# 2_OTHER.net
KiCad netlist of a schematic drawn in Altium Designer
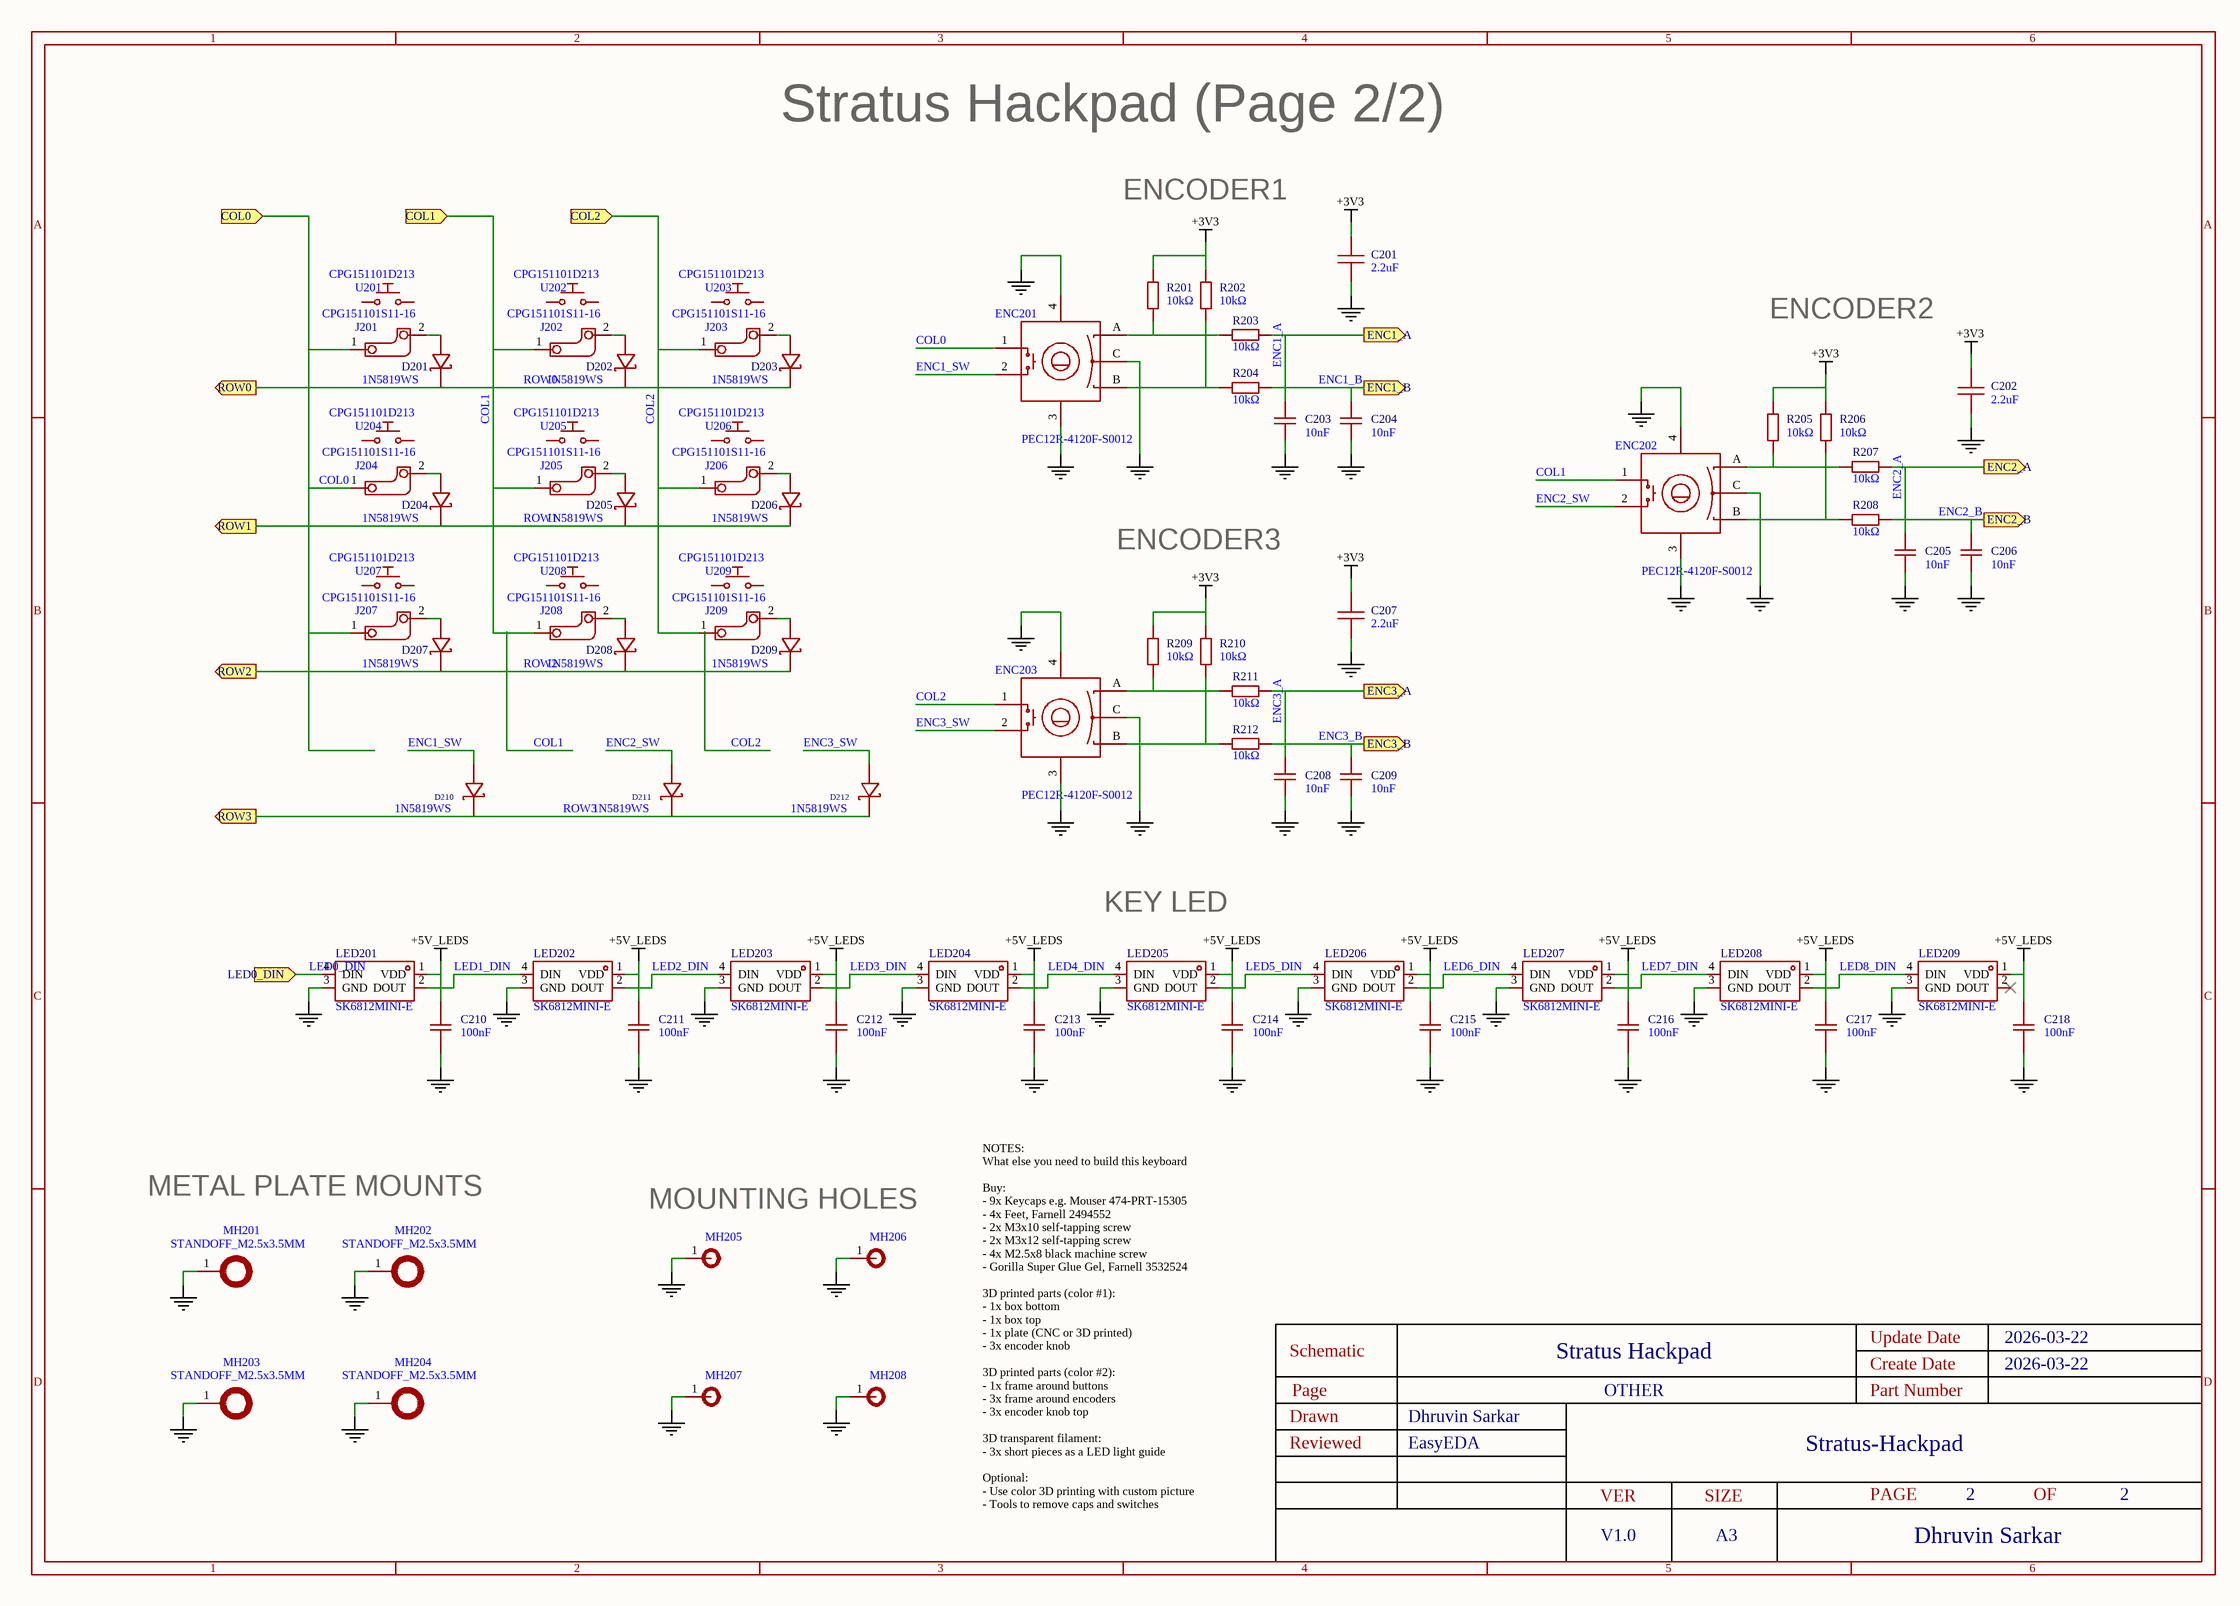
[diagram p0: 2_OTHER.schdoc]

(export (version "E")
  (design (tool "Eeschema 10.0.6"))
  (components
    (comp (ref "C201")
      (value "2.2uF")
      (footprint "C0402")
      (fields
        (field (name "MANUFACTURER") "SAMSUNG(三星)")
        (field (name "MANUFACTURER PART") "CL05A225MQ5NSNC")
        (field (name "TOLERANCE") "±20%")
      )
      (libsource (lib "altium-import") (part "root_1_CL05A225MQ5NSNC_"))
    )
    (comp (ref "C202")
      (value "2.2uF")
      (footprint "C0402")
      (fields
        (field (name "MANUFACTURER") "SAMSUNG(三星)")
        (field (name "MANUFACTURER PART") "CL05A225MQ5NSNC")
        (field (name "TOLERANCE") "±20%")
      )
      (libsource (lib "altium-import") (part "root_1_CL05A225MQ5NSNC_"))
    )
    (comp (ref "C203")
      (value "10nF")
      (footprint "C0402")
      (fields
        (field (name "MANUFACTURER") "SAMSUNG(三星)")
        (field (name "MANUFACTURER PART") "CL05B103KB5NNNC")
        (field (name "TOLERANCE") "±10%")
      )
      (libsource (lib "altium-import") (part "root_1_CL05B103KB5NNNC_"))
    )
    (comp (ref "C204")
      (value "10nF")
      (footprint "C0402")
      (fields
        (field (name "MANUFACTURER") "SAMSUNG(三星)")
        (field (name "MANUFACTURER PART") "CL05B103KB5NNNC")
        (field (name "TOLERANCE") "±10%")
      )
      (libsource (lib "altium-import") (part "root_1_CL05B103KB5NNNC_"))
    )
    (comp (ref "C205")
      (value "10nF")
      (footprint "C0402")
      (fields
        (field (name "MANUFACTURER") "SAMSUNG(三星)")
        (field (name "MANUFACTURER PART") "CL05B103KB5NNNC")
        (field (name "TOLERANCE") "±10%")
      )
      (libsource (lib "altium-import") (part "root_1_CL05B103KB5NNNC_"))
    )
    (comp (ref "C206")
      (value "10nF")
      (footprint "C0402")
      (fields
        (field (name "MANUFACTURER") "SAMSUNG(三星)")
        (field (name "MANUFACTURER PART") "CL05B103KB5NNNC")
        (field (name "TOLERANCE") "±10%")
      )
      (libsource (lib "altium-import") (part "root_1_CL05B103KB5NNNC_"))
    )
    (comp (ref "C207")
      (value "2.2uF")
      (footprint "C0402")
      (fields
        (field (name "MANUFACTURER") "SAMSUNG(三星)")
        (field (name "MANUFACTURER PART") "CL05A225MQ5NSNC")
        (field (name "TOLERANCE") "±20%")
      )
      (libsource (lib "altium-import") (part "root_1_CL05A225MQ5NSNC_"))
    )
    (comp (ref "C208")
      (value "10nF")
      (footprint "C0402")
      (fields
        (field (name "MANUFACTURER") "SAMSUNG(三星)")
        (field (name "MANUFACTURER PART") "CL05B103KB5NNNC")
        (field (name "TOLERANCE") "±10%")
      )
      (libsource (lib "altium-import") (part "root_1_CL05B103KB5NNNC_"))
    )
    (comp (ref "C209")
      (value "10nF")
      (footprint "C0402")
      (fields
        (field (name "MANUFACTURER") "SAMSUNG(三星)")
        (field (name "MANUFACTURER PART") "CL05B103KB5NNNC")
        (field (name "TOLERANCE") "±10%")
      )
      (libsource (lib "altium-import") (part "root_1_CL05B103KB5NNNC_"))
    )
    (comp (ref "C210")
      (value "100nF")
      (footprint "C0402")
      (fields
        (field (name "MANUFACTURER") "SAMSUNG(三星)")
        (field (name "MANUFACTURER PART") "CL05B104KO5NNNC")
        (field (name "TOLERANCE") "±10%")
      )
      (libsource (lib "altium-import") (part "root_1_CL05B104KO5NNNC_"))
    )
    (comp (ref "C211")
      (value "100nF")
      (footprint "C0402")
      (fields
        (field (name "MANUFACTURER") "SAMSUNG(三星)")
        (field (name "MANUFACTURER PART") "CL05B104KO5NNNC")
        (field (name "TOLERANCE") "±10%")
      )
      (libsource (lib "altium-import") (part "root_1_CL05B104KO5NNNC_"))
    )
    (comp (ref "C212")
      (value "100nF")
      (footprint "C0402")
      (fields
        (field (name "MANUFACTURER") "SAMSUNG(三星)")
        (field (name "MANUFACTURER PART") "CL05B104KO5NNNC")
        (field (name "TOLERANCE") "±10%")
      )
      (libsource (lib "altium-import") (part "root_1_CL05B104KO5NNNC_"))
    )
    (comp (ref "C213")
      (value "100nF")
      (footprint "C0402")
      (fields
        (field (name "MANUFACTURER") "SAMSUNG(三星)")
        (field (name "MANUFACTURER PART") "CL05B104KO5NNNC")
        (field (name "TOLERANCE") "±10%")
      )
      (libsource (lib "altium-import") (part "root_1_CL05B104KO5NNNC_"))
    )
    (comp (ref "C214")
      (value "100nF")
      (footprint "C0402")
      (fields
        (field (name "MANUFACTURER") "SAMSUNG(三星)")
        (field (name "MANUFACTURER PART") "CL05B104KO5NNNC")
        (field (name "TOLERANCE") "±10%")
      )
      (libsource (lib "altium-import") (part "root_1_CL05B104KO5NNNC_"))
    )
    (comp (ref "C215")
      (value "100nF")
      (footprint "C0402")
      (fields
        (field (name "MANUFACTURER") "SAMSUNG(三星)")
        (field (name "MANUFACTURER PART") "CL05B104KO5NNNC")
        (field (name "TOLERANCE") "±10%")
      )
      (libsource (lib "altium-import") (part "root_1_CL05B104KO5NNNC_"))
    )
    (comp (ref "C216")
      (value "100nF")
      (footprint "C0402")
      (fields
        (field (name "MANUFACTURER") "SAMSUNG(三星)")
        (field (name "MANUFACTURER PART") "CL05B104KO5NNNC")
        (field (name "TOLERANCE") "±10%")
      )
      (libsource (lib "altium-import") (part "root_1_CL05B104KO5NNNC_"))
    )
    (comp (ref "C217")
      (value "100nF")
      (footprint "C0402")
      (fields
        (field (name "MANUFACTURER") "SAMSUNG(三星)")
        (field (name "MANUFACTURER PART") "CL05B104KO5NNNC")
        (field (name "TOLERANCE") "±10%")
      )
      (libsource (lib "altium-import") (part "root_1_CL05B104KO5NNNC_"))
    )
    (comp (ref "C218")
      (value "100nF")
      (footprint "C0402")
      (fields
        (field (name "MANUFACTURER") "SAMSUNG(三星)")
        (field (name "MANUFACTURER PART") "CL05B104KO5NNNC")
        (field (name "TOLERANCE") "±10%")
      )
      (libsource (lib "altium-import") (part "root_1_CL05B104KO5NNNC_"))
    )
    (comp (ref "D201")
      (value "1N5819WS")
      (footprint "SOD-323_L1.8-W1.3-LS2.5-RD")
      (fields (field (name "MANUFACTURER") "Hottech(合科泰)"))
      (libsource (lib "altium-import") (part "root_1_1N5819WS_C191023_"))
    )
    (comp (ref "D202")
      (value "1N5819WS")
      (footprint "SOD-323_L1.8-W1.3-LS2.5-RD")
      (fields (field (name "MANUFACTURER") "Hottech(合科泰)"))
      (libsource (lib "altium-import") (part "root_1_1N5819WS_C191023_"))
    )
    (comp (ref "D203")
      (value "1N5819WS")
      (footprint "SOD-323_L1.8-W1.3-LS2.5-RD")
      (fields (field (name "MANUFACTURER") "Hottech(合科泰)"))
      (libsource (lib "altium-import") (part "root_1_1N5819WS_C191023_"))
    )
    (comp (ref "D204")
      (value "1N5819WS")
      (footprint "SOD-323_L1.8-W1.3-LS2.5-RD")
      (fields (field (name "MANUFACTURER") "Hottech(合科泰)"))
      (libsource (lib "altium-import") (part "root_1_1N5819WS_C191023_"))
    )
    (comp (ref "D205")
      (value "1N5819WS")
      (footprint "SOD-323_L1.8-W1.3-LS2.5-RD")
      (fields (field (name "MANUFACTURER") "Hottech(合科泰)"))
      (libsource (lib "altium-import") (part "root_1_1N5819WS_C191023_"))
    )
    (comp (ref "D206")
      (value "1N5819WS")
      (footprint "SOD-323_L1.8-W1.3-LS2.5-RD")
      (fields (field (name "MANUFACTURER") "Hottech(合科泰)"))
      (libsource (lib "altium-import") (part "root_1_1N5819WS_C191023_"))
    )
    (comp (ref "D207")
      (value "1N5819WS")
      (footprint "SOD-323_L1.8-W1.3-LS2.5-RD")
      (fields (field (name "MANUFACTURER") "Hottech(合科泰)"))
      (libsource (lib "altium-import") (part "root_1_1N5819WS_C191023_"))
    )
    (comp (ref "D208")
      (value "1N5819WS")
      (footprint "SOD-323_L1.8-W1.3-LS2.5-RD")
      (fields (field (name "MANUFACTURER") "Hottech(合科泰)"))
      (libsource (lib "altium-import") (part "root_1_1N5819WS_C191023_"))
    )
    (comp (ref "D209")
      (value "1N5819WS")
      (footprint "SOD-323_L1.8-W1.3-LS2.5-RD")
      (fields (field (name "MANUFACTURER") "Hottech(合科泰)"))
      (libsource (lib "altium-import") (part "root_1_1N5819WS_C191023_"))
    )
    (comp (ref "D210")
      (value "1N5819WS")
      (footprint "SOD-323_L1.8-W1.3-LS2.5-RD")
      (fields (field (name "MANUFACTURER") "Hottech(合科泰)"))
      (libsource (lib "altium-import") (part "root_1_1N5819WS_C191023_"))
    )
    (comp (ref "D211")
      (value "1N5819WS")
      (footprint "SOD-323_L1.8-W1.3-LS2.5-RD")
      (fields (field (name "MANUFACTURER") "Hottech(合科泰)"))
      (libsource (lib "altium-import") (part "root_1_1N5819WS_C191023_"))
    )
    (comp (ref "D212")
      (value "1N5819WS")
      (footprint "SOD-323_L1.8-W1.3-LS2.5-RD")
      (fields (field (name "MANUFACTURER") "Hottech(合科泰)"))
      (libsource (lib "altium-import") (part "root_1_1N5819WS_C191023_"))
    )
    (comp (ref "ENC201")
      (value "PEC12R-4120F-S0012")
      (footprint "SW-TH_PEC12R-4120F-S0012_1")
      (fields (field (name "MANUFACTURER") "BOURNS"))
      (libsource (lib "altium-import") (part "root_3_mirrored_PEC12R-4120F-S0012_RF_v1.0_"))
    )
    (comp (ref "ENC202")
      (value "PEC12R-4120F-S0012")
      (footprint "SW-TH_PEC12R-4120F-S0012_1")
      (fields (field (name "MANUFACTURER") "BOURNS"))
      (libsource (lib "altium-import") (part "root_3_mirrored_PEC12R-4120F-S0012_RF_v1.0_"))
    )
    (comp (ref "ENC203")
      (value "PEC12R-4120F-S0012")
      (footprint "SW-TH_PEC12R-4120F-S0012_1")
      (fields (field (name "MANUFACTURER") "BOURNS"))
      (libsource (lib "altium-import") (part "root_3_mirrored_PEC12R-4120F-S0012_RF_v1.0_"))
    )
    (comp (ref "J201")
      (value "CPG151101S11-16")
      (footprint "SMD_KEYBOARD-SW")
      (fields (field (name "MANUFACTURER") "Kailh(凯华)"))
      (libsource (lib "altium-import") (part "root_0_CPG151101S11-16_DS_v1.0_"))
    )
    (comp (ref "J202")
      (value "CPG151101S11-16")
      (footprint "SMD_KEYBOARD-SW")
      (fields (field (name "MANUFACTURER") "Kailh(凯华)"))
      (libsource (lib "altium-import") (part "root_0_CPG151101S11-16_DS_v1.0_"))
    )
    (comp (ref "J203")
      (value "CPG151101S11-16")
      (footprint "SMD_KEYBOARD-SW")
      (fields (field (name "MANUFACTURER") "Kailh(凯华)"))
      (libsource (lib "altium-import") (part "root_0_CPG151101S11-16_DS_v1.0_"))
    )
    (comp (ref "J204")
      (value "CPG151101S11-16")
      (footprint "SMD_KEYBOARD-SW")
      (fields (field (name "MANUFACTURER") "Kailh(凯华)"))
      (libsource (lib "altium-import") (part "root_0_CPG151101S11-16_DS_v1.0_"))
    )
    (comp (ref "J205")
      (value "CPG151101S11-16")
      (footprint "SMD_KEYBOARD-SW")
      (fields (field (name "MANUFACTURER") "Kailh(凯华)"))
      (libsource (lib "altium-import") (part "root_0_CPG151101S11-16_DS_v1.0_"))
    )
    (comp (ref "J206")
      (value "CPG151101S11-16")
      (footprint "SMD_KEYBOARD-SW")
      (fields (field (name "MANUFACTURER") "Kailh(凯华)"))
      (libsource (lib "altium-import") (part "root_0_CPG151101S11-16_DS_v1.0_"))
    )
    (comp (ref "J207")
      (value "CPG151101S11-16")
      (footprint "SMD_KEYBOARD-SW")
      (fields (field (name "MANUFACTURER") "Kailh(凯华)"))
      (libsource (lib "altium-import") (part "root_0_CPG151101S11-16_DS_v1.0_"))
    )
    (comp (ref "J208")
      (value "CPG151101S11-16")
      (footprint "SMD_KEYBOARD-SW")
      (fields (field (name "MANUFACTURER") "Kailh(凯华)"))
      (libsource (lib "altium-import") (part "root_0_CPG151101S11-16_DS_v1.0_"))
    )
    (comp (ref "J209")
      (value "CPG151101S11-16")
      (footprint "SMD_KEYBOARD-SW")
      (fields (field (name "MANUFACTURER") "Kailh(凯华)"))
      (libsource (lib "altium-import") (part "root_0_CPG151101S11-16_DS_v1.0_"))
    )
    (comp (ref "LED201")
      (value "SK6812MINI-E")
      (footprint "LED-SMD_L3.2-W2.8-TR")
      (fields (field (name "MANUFACTURER") "欧思科光电"))
      (libsource (lib "altium-import") (part "root_0_mirrored_SK6812MINI-E_C5149201_"))
    )
    (comp (ref "LED202")
      (value "SK6812MINI-E")
      (footprint "LED-SMD_L3.2-W2.8-TR")
      (fields (field (name "MANUFACTURER") "欧思科光电"))
      (libsource (lib "altium-import") (part "root_0_mirrored_SK6812MINI-E_C5149201_"))
    )
    (comp (ref "LED203")
      (value "SK6812MINI-E")
      (footprint "LED-SMD_L3.2-W2.8-TR")
      (fields (field (name "MANUFACTURER") "欧思科光电"))
      (libsource (lib "altium-import") (part "root_0_mirrored_SK6812MINI-E_C5149201_"))
    )
    (comp (ref "LED204")
      (value "SK6812MINI-E")
      (footprint "LED-SMD_L3.2-W2.8-TR")
      (fields (field (name "MANUFACTURER") "欧思科光电"))
      (libsource (lib "altium-import") (part "root_0_mirrored_SK6812MINI-E_C5149201_"))
    )
    (comp (ref "LED205")
      (value "SK6812MINI-E")
      (footprint "LED-SMD_L3.2-W2.8-TR")
      (fields (field (name "MANUFACTURER") "欧思科光电"))
      (libsource (lib "altium-import") (part "root_0_mirrored_SK6812MINI-E_C5149201_"))
    )
    (comp (ref "LED206")
      (value "SK6812MINI-E")
      (footprint "LED-SMD_L3.2-W2.8-TR")
      (fields (field (name "MANUFACTURER") "欧思科光电"))
      (libsource (lib "altium-import") (part "root_0_mirrored_SK6812MINI-E_C5149201_"))
    )
    (comp (ref "LED207")
      (value "SK6812MINI-E")
      (footprint "LED-SMD_L3.2-W2.8-TR")
      (fields (field (name "MANUFACTURER") "欧思科光电"))
      (libsource (lib "altium-import") (part "root_0_mirrored_SK6812MINI-E_C5149201_"))
    )
    (comp (ref "LED208")
      (value "SK6812MINI-E")
      (footprint "LED-SMD_L3.2-W2.8-TR")
      (fields (field (name "MANUFACTURER") "欧思科光电"))
      (libsource (lib "altium-import") (part "root_0_mirrored_SK6812MINI-E_C5149201_"))
    )
    (comp (ref "LED209")
      (value "SK6812MINI-E")
      (footprint "LED-SMD_L3.2-W2.8-TR")
      (fields (field (name "MANUFACTURER") "欧思科光电"))
      (libsource (lib "altium-import") (part "root_0_mirrored_SK6812MINI-E_C5149201_"))
    )
    (comp (ref "MH201")
      (value "STANDOFF_M2.5x3.5MM")
      (footprint "STANDOFF_M2.5x3.5MM_RF_v1.0")
      (fields (field (name "MANUFACTURER") "WURTH ELEKTRONIK") (field (name "PART NUMBER") "9774035151R"))
      (libsource (lib "altium-import") (part "root_0_9774035151R_RF_v1.0_"))
    )
    (comp (ref "MH202")
      (value "STANDOFF_M2.5x3.5MM")
      (footprint "STANDOFF_M2.5x3.5MM_RF_v1.0")
      (fields (field (name "MANUFACTURER") "WURTH ELEKTRONIK") (field (name "PART NUMBER") "9774035151R"))
      (libsource (lib "altium-import") (part "root_0_9774035151R_RF_v1.0_"))
    )
    (comp (ref "MH203")
      (value "STANDOFF_M2.5x3.5MM")
      (footprint "STANDOFF_M2.5x3.5MM_RF_v1.0")
      (fields (field (name "MANUFACTURER") "WURTH ELEKTRONIK") (field (name "PART NUMBER") "9774035151R"))
      (libsource (lib "altium-import") (part "root_0_9774035151R_RF_v1.0_"))
    )
    (comp (ref "MH204")
      (value "STANDOFF_M2.5x3.5MM")
      (footprint "STANDOFF_M2.5x3.5MM_RF_v1.0")
      (fields (field (name "MANUFACTURER") "WURTH ELEKTRONIK") (field (name "PART NUMBER") "9774035151R"))
      (libsource (lib "altium-import") (part "root_0_9774035151R_RF_v1.0_"))
    )
    (comp (ref "MH205")
      (value "~")
      (footprint "MH_7.5X3.2MM_RF_v1.0")
      (libsource (lib "altium-import") (part "root_0_MH_7.5X3.2MM_RF_v1.0_"))
    )
    (comp (ref "MH206")
      (value "~")
      (footprint "MH_7.5X3.2MM_RF_v1.0")
      (libsource (lib "altium-import") (part "root_0_MH_7.5X3.2MM_RF_v1.0_"))
    )
    (comp (ref "MH207")
      (value "~")
      (footprint "MH_7.5X3.2MM_RF_v1.0")
      (libsource (lib "altium-import") (part "root_0_MH_7.5X3.2MM_RF_v1.0_"))
    )
    (comp (ref "MH208")
      (value "~")
      (footprint "MH_7.5X3.2MM_RF_v1.0")
      (libsource (lib "altium-import") (part "root_0_MH_7.5X3.2MM_RF_v1.0_"))
    )
    (comp (ref "R201")
      (value "10kΩ")
      (footprint "R0402")
      (fields
        (field (name "MANUFACTURER") "UNI-ROYAL(厚声)")
        (field (name "MANUFACTURER PART") "0402WGF1002TCE")
        (field (name "TOLERANCE") "±1%")
      )
      (libsource (lib "altium-import") (part "root_1_0402WGF1002TCE_"))
    )
    (comp (ref "R202")
      (value "10kΩ")
      (footprint "R0402")
      (fields
        (field (name "MANUFACTURER") "UNI-ROYAL(厚声)")
        (field (name "MANUFACTURER PART") "0402WGF1002TCE")
        (field (name "TOLERANCE") "±1%")
      )
      (libsource (lib "altium-import") (part "root_1_0402WGF1002TCE_"))
    )
    (comp (ref "R203")
      (value "10kΩ")
      (footprint "R0402")
      (fields
        (field (name "MANUFACTURER") "UNI-ROYAL(厚声)")
        (field (name "MANUFACTURER PART") "0402WGF1002TCE")
        (field (name "TOLERANCE") "±1%")
      )
      (libsource (lib "altium-import") (part "root_2_0402WGF1002TCE_"))
    )
    (comp (ref "R204")
      (value "10kΩ")
      (footprint "R0402")
      (fields
        (field (name "MANUFACTURER") "UNI-ROYAL(厚声)")
        (field (name "MANUFACTURER PART") "0402WGF1002TCE")
        (field (name "TOLERANCE") "±1%")
      )
      (libsource (lib "altium-import") (part "root_2_0402WGF1002TCE_"))
    )
    (comp (ref "R205")
      (value "10kΩ")
      (footprint "R0402")
      (fields
        (field (name "MANUFACTURER") "UNI-ROYAL(厚声)")
        (field (name "MANUFACTURER PART") "0402WGF1002TCE")
        (field (name "TOLERANCE") "±1%")
      )
      (libsource (lib "altium-import") (part "root_1_0402WGF1002TCE_"))
    )
    (comp (ref "R206")
      (value "10kΩ")
      (footprint "R0402")
      (fields
        (field (name "MANUFACTURER") "UNI-ROYAL(厚声)")
        (field (name "MANUFACTURER PART") "0402WGF1002TCE")
        (field (name "TOLERANCE") "±1%")
      )
      (libsource (lib "altium-import") (part "root_1_0402WGF1002TCE_"))
    )
    (comp (ref "R207")
      (value "10kΩ")
      (footprint "R0402")
      (fields
        (field (name "MANUFACTURER") "UNI-ROYAL(厚声)")
        (field (name "MANUFACTURER PART") "0402WGF1002TCE")
        (field (name "TOLERANCE") "±1%")
      )
      (libsource (lib "altium-import") (part "root_2_0402WGF1002TCE_"))
    )
    (comp (ref "R208")
      (value "10kΩ")
      (footprint "R0402")
      (fields
        (field (name "MANUFACTURER") "UNI-ROYAL(厚声)")
        (field (name "MANUFACTURER PART") "0402WGF1002TCE")
        (field (name "TOLERANCE") "±1%")
      )
      (libsource (lib "altium-import") (part "root_2_0402WGF1002TCE_"))
    )
    (comp (ref "R209")
      (value "10kΩ")
      (footprint "R0402")
      (fields
        (field (name "MANUFACTURER") "UNI-ROYAL(厚声)")
        (field (name "MANUFACTURER PART") "0402WGF1002TCE")
        (field (name "TOLERANCE") "±1%")
      )
      (libsource (lib "altium-import") (part "root_1_0402WGF1002TCE_"))
    )
    (comp (ref "R210")
      (value "10kΩ")
      (footprint "R0402")
      (fields
        (field (name "MANUFACTURER") "UNI-ROYAL(厚声)")
        (field (name "MANUFACTURER PART") "0402WGF1002TCE")
        (field (name "TOLERANCE") "±1%")
      )
      (libsource (lib "altium-import") (part "root_1_0402WGF1002TCE_"))
    )
    (comp (ref "R211")
      (value "10kΩ")
      (footprint "R0402")
      (fields
        (field (name "MANUFACTURER") "UNI-ROYAL(厚声)")
        (field (name "MANUFACTURER PART") "0402WGF1002TCE")
        (field (name "TOLERANCE") "±1%")
      )
      (libsource (lib "altium-import") (part "root_2_0402WGF1002TCE_"))
    )
    (comp (ref "R212")
      (value "10kΩ")
      (footprint "R0402")
      (fields
        (field (name "MANUFACTURER") "UNI-ROYAL(厚声)")
        (field (name "MANUFACTURER PART") "0402WGF1002TCE")
        (field (name "TOLERANCE") "±1%")
      )
      (libsource (lib "altium-import") (part "root_2_0402WGF1002TCE_"))
    )
    (comp (ref "U201")
      (value "CPG151101D213")
      (footprint "KEY-TH_CPG151101D21X")
      (fields (field (name "MANUFACTURER") "Kailh(凯华)"))
      (libsource (lib "altium-import") (part "root_0_CPG151101D213_DS_v1.0_"))
    )
    (comp (ref "U202")
      (value "CPG151101D213")
      (footprint "KEY-TH_CPG151101D21X")
      (fields (field (name "MANUFACTURER") "Kailh(凯华)"))
      (libsource (lib "altium-import") (part "root_0_CPG151101D213_DS_v1.0_"))
    )
    (comp (ref "U203")
      (value "CPG151101D213")
      (footprint "KEY-TH_CPG151101D21X")
      (fields (field (name "MANUFACTURER") "Kailh(凯华)"))
      (libsource (lib "altium-import") (part "root_0_CPG151101D213_DS_v1.0_"))
    )
    (comp (ref "U204")
      (value "CPG151101D213")
      (footprint "KEY-TH_CPG151101D21X")
      (fields (field (name "MANUFACTURER") "Kailh(凯华)"))
      (libsource (lib "altium-import") (part "root_0_CPG151101D213_DS_v1.0_"))
    )
    (comp (ref "U205")
      (value "CPG151101D213")
      (footprint "KEY-TH_CPG151101D21X")
      (fields (field (name "MANUFACTURER") "Kailh(凯华)"))
      (libsource (lib "altium-import") (part "root_0_CPG151101D213_DS_v1.0_"))
    )
    (comp (ref "U206")
      (value "CPG151101D213")
      (footprint "KEY-TH_CPG151101D21X")
      (fields (field (name "MANUFACTURER") "Kailh(凯华)"))
      (libsource (lib "altium-import") (part "root_0_CPG151101D213_DS_v1.0_"))
    )
    (comp (ref "U207")
      (value "CPG151101D213")
      (footprint "KEY-TH_CPG151101D21X")
      (fields (field (name "MANUFACTURER") "Kailh(凯华)"))
      (libsource (lib "altium-import") (part "root_0_CPG151101D213_DS_v1.0_"))
    )
    (comp (ref "U208")
      (value "CPG151101D213")
      (footprint "KEY-TH_CPG151101D21X")
      (fields (field (name "MANUFACTURER") "Kailh(凯华)"))
      (libsource (lib "altium-import") (part "root_0_CPG151101D213_DS_v1.0_"))
    )
    (comp (ref "U209")
      (value "CPG151101D213")
      (footprint "KEY-TH_CPG151101D21X")
      (fields (field (name "MANUFACTURER") "Kailh(凯华)"))
      (libsource (lib "altium-import") (part "root_0_CPG151101D213_DS_v1.0_"))
    )
  )
  (nets
    (net (code "1") (name "+3V3") (class "Default")
      (node (ref "C201") (pin "2") (pinfunction "2_2") (pintype "passive"))
      (node (ref "C202") (pin "2") (pinfunction "2_2") (pintype "passive"))
      (node (ref "C207") (pin "2") (pinfunction "2_2") (pintype "passive"))
      (node (ref "R201") (pin "2") (pinfunction "2_2") (pintype "passive"))
      (node (ref "R202") (pin "2") (pinfunction "2_2") (pintype "passive"))
      (node (ref "R205") (pin "2") (pinfunction "2_2") (pintype "passive"))
      (node (ref "R206") (pin "2") (pinfunction "2_2") (pintype "passive"))
      (node (ref "R209") (pin "2") (pinfunction "2_2") (pintype "passive"))
      (node (ref "R210") (pin "2") (pinfunction "2_2") (pintype "passive"))
    )
    (net (code "2") (name "+5V_LEDS") (class "Default")
      (node (ref "C210") (pin "2") (pinfunction "2_2") (pintype "passive"))
      (node (ref "C211") (pin "2") (pinfunction "2_2") (pintype "passive"))
      (node (ref "C212") (pin "2") (pinfunction "2_2") (pintype "passive"))
      (node (ref "C213") (pin "2") (pinfunction "2_2") (pintype "passive"))
      (node (ref "C214") (pin "2") (pinfunction "2_2") (pintype "passive"))
      (node (ref "C215") (pin "2") (pinfunction "2_2") (pintype "passive"))
      (node (ref "C216") (pin "2") (pinfunction "2_2") (pintype "passive"))
      (node (ref "C217") (pin "2") (pinfunction "2_2") (pintype "passive"))
      (node (ref "C218") (pin "2") (pinfunction "2_2") (pintype "passive"))
      (node (ref "LED201") (pin "1") (pinfunction "VDD_1") (pintype "passive"))
      (node (ref "LED202") (pin "1") (pinfunction "VDD_1") (pintype "passive"))
      (node (ref "LED203") (pin "1") (pinfunction "VDD_1") (pintype "passive"))
      (node (ref "LED204") (pin "1") (pinfunction "VDD_1") (pintype "passive"))
      (node (ref "LED205") (pin "1") (pinfunction "VDD_1") (pintype "passive"))
      (node (ref "LED206") (pin "1") (pinfunction "VDD_1") (pintype "passive"))
      (node (ref "LED207") (pin "1") (pinfunction "VDD_1") (pintype "passive"))
      (node (ref "LED208") (pin "1") (pinfunction "VDD_1") (pintype "passive"))
      (node (ref "LED209") (pin "1") (pinfunction "VDD_1") (pintype "passive"))
    )
    (net (code "3") (name "/COL0") (class "Default")
      (node (ref "ENC201") (pin "1") (pinfunction "1_1") (pintype "passive"))
      (node (ref "J201") (pin "1") (pinfunction "1_1") (pintype "passive"))
      (node (ref "J204") (pin "1") (pinfunction "1_1") (pintype "passive"))
      (node (ref "J207") (pin "1") (pinfunction "1_1") (pintype "passive"))
    )
    (net (code "4") (name "/COL1") (class "Default")
      (node (ref "ENC202") (pin "1") (pinfunction "1_1") (pintype "passive"))
      (node (ref "J202") (pin "1") (pinfunction "1_1") (pintype "passive"))
      (node (ref "J205") (pin "1") (pinfunction "1_1") (pintype "passive"))
      (node (ref "J208") (pin "1") (pinfunction "1_1") (pintype "passive"))
    )
    (net (code "5") (name "/COL2") (class "Default")
      (node (ref "ENC203") (pin "1") (pinfunction "1_1") (pintype "passive"))
      (node (ref "J203") (pin "1") (pinfunction "1_1") (pintype "passive"))
      (node (ref "J206") (pin "1") (pinfunction "1_1") (pintype "passive"))
      (node (ref "J209") (pin "1") (pinfunction "1_1") (pintype "passive"))
    )
    (net (code "6") (name "/ENC1_A") (class "Default")
      (node (ref "C203") (pin "2") (pinfunction "2_2") (pintype "passive"))
      (node (ref "R203") (pin "1") (pinfunction "1_1") (pintype "passive"))
    )
    (net (code "7") (name "/ENC1_B") (class "Default")
      (node (ref "C204") (pin "2") (pinfunction "2_2") (pintype "passive"))
      (node (ref "R204") (pin "1") (pinfunction "1_1") (pintype "passive"))
    )
    (net (code "8") (name "/ENC1_SW") (class "Default")
      (node (ref "D210") (pin "2") (pinfunction "A_2") (pintype "passive"))
      (node (ref "ENC201") (pin "2") (pinfunction "2_2") (pintype "passive"))
    )
    (net (code "9") (name "/ENC2_A") (class "Default")
      (node (ref "C205") (pin "2") (pinfunction "2_2") (pintype "passive"))
      (node (ref "R207") (pin "1") (pinfunction "1_1") (pintype "passive"))
    )
    (net (code "10") (name "/ENC2_B") (class "Default")
      (node (ref "C206") (pin "2") (pinfunction "2_2") (pintype "passive"))
      (node (ref "R208") (pin "1") (pinfunction "1_1") (pintype "passive"))
    )
    (net (code "11") (name "/ENC2_SW") (class "Default")
      (node (ref "D211") (pin "2") (pinfunction "A_2") (pintype "passive"))
      (node (ref "ENC202") (pin "2") (pinfunction "2_2") (pintype "passive"))
    )
    (net (code "12") (name "/ENC3_A") (class "Default")
      (node (ref "C208") (pin "2") (pinfunction "2_2") (pintype "passive"))
      (node (ref "R211") (pin "1") (pinfunction "1_1") (pintype "passive"))
    )
    (net (code "13") (name "/ENC3_B") (class "Default")
      (node (ref "C209") (pin "2") (pinfunction "2_2") (pintype "passive"))
      (node (ref "R212") (pin "1") (pinfunction "1_1") (pintype "passive"))
    )
    (net (code "14") (name "/ENC3_SW") (class "Default")
      (node (ref "D212") (pin "2") (pinfunction "A_2") (pintype "passive"))
      (node (ref "ENC203") (pin "2") (pinfunction "2_2") (pintype "passive"))
    )
    (net (code "15") (name "/LED0_DIN") (class "Default")
      (node (ref "LED201") (pin "4") (pinfunction "DIN_4") (pintype "passive"))
    )
    (net (code "16") (name "/LED1_DIN") (class "Default")
      (node (ref "LED201") (pin "2") (pinfunction "DOUT_2") (pintype "passive"))
      (node (ref "LED202") (pin "4") (pinfunction "DIN_4") (pintype "passive"))
    )
    (net (code "17") (name "/LED2_DIN") (class "Default")
      (node (ref "LED202") (pin "2") (pinfunction "DOUT_2") (pintype "passive"))
      (node (ref "LED203") (pin "4") (pinfunction "DIN_4") (pintype "passive"))
    )
    (net (code "18") (name "/LED3_DIN") (class "Default")
      (node (ref "LED203") (pin "2") (pinfunction "DOUT_2") (pintype "passive"))
      (node (ref "LED204") (pin "4") (pinfunction "DIN_4") (pintype "passive"))
    )
    (net (code "19") (name "/LED4_DIN") (class "Default")
      (node (ref "LED204") (pin "2") (pinfunction "DOUT_2") (pintype "passive"))
      (node (ref "LED205") (pin "4") (pinfunction "DIN_4") (pintype "passive"))
    )
    (net (code "20") (name "/LED5_DIN") (class "Default")
      (node (ref "LED205") (pin "2") (pinfunction "DOUT_2") (pintype "passive"))
      (node (ref "LED206") (pin "4") (pinfunction "DIN_4") (pintype "passive"))
    )
    (net (code "21") (name "/LED6_DIN") (class "Default")
      (node (ref "LED206") (pin "2") (pinfunction "DOUT_2") (pintype "passive"))
      (node (ref "LED207") (pin "4") (pinfunction "DIN_4") (pintype "passive"))
    )
    (net (code "22") (name "/LED7_DIN") (class "Default")
      (node (ref "LED207") (pin "2") (pinfunction "DOUT_2") (pintype "passive"))
      (node (ref "LED208") (pin "4") (pinfunction "DIN_4") (pintype "passive"))
    )
    (net (code "23") (name "/LED8_DIN") (class "Default")
      (node (ref "LED208") (pin "2") (pinfunction "DOUT_2") (pintype "passive"))
      (node (ref "LED209") (pin "4") (pinfunction "DIN_4") (pintype "passive"))
    )
    (net (code "24") (name "/ROW0") (class "Default")
      (node (ref "D201") (pin "1") (pinfunction "K_1") (pintype "passive"))
      (node (ref "D202") (pin "1") (pinfunction "K_1") (pintype "passive"))
      (node (ref "D203") (pin "1") (pinfunction "K_1") (pintype "passive"))
    )
    (net (code "25") (name "/ROW1") (class "Default")
      (node (ref "D204") (pin "1") (pinfunction "K_1") (pintype "passive"))
      (node (ref "D205") (pin "1") (pinfunction "K_1") (pintype "passive"))
      (node (ref "D206") (pin "1") (pinfunction "K_1") (pintype "passive"))
    )
    (net (code "26") (name "/ROW2") (class "Default")
      (node (ref "D207") (pin "1") (pinfunction "K_1") (pintype "passive"))
      (node (ref "D208") (pin "1") (pinfunction "K_1") (pintype "passive"))
      (node (ref "D209") (pin "1") (pinfunction "K_1") (pintype "passive"))
    )
    (net (code "27") (name "/ROW3") (class "Default")
      (node (ref "D210") (pin "1") (pinfunction "K_1") (pintype "passive"))
      (node (ref "D211") (pin "1") (pinfunction "K_1") (pintype "passive"))
      (node (ref "D212") (pin "1") (pinfunction "K_1") (pintype "passive"))
    )
    (net (code "28") (name "GND") (class "Default")
      (node (ref "C201") (pin "1") (pinfunction "1_1") (pintype "passive"))
      (node (ref "C202") (pin "1") (pinfunction "1_1") (pintype "passive"))
      (node (ref "C203") (pin "1") (pinfunction "1_1") (pintype "passive"))
      (node (ref "C204") (pin "1") (pinfunction "1_1") (pintype "passive"))
      (node (ref "C205") (pin "1") (pinfunction "1_1") (pintype "passive"))
      (node (ref "C206") (pin "1") (pinfunction "1_1") (pintype "passive"))
      (node (ref "C207") (pin "1") (pinfunction "1_1") (pintype "passive"))
      (node (ref "C208") (pin "1") (pinfunction "1_1") (pintype "passive"))
      (node (ref "C209") (pin "1") (pinfunction "1_1") (pintype "passive"))
      (node (ref "C210") (pin "1") (pinfunction "1_1") (pintype "passive"))
      (node (ref "C211") (pin "1") (pinfunction "1_1") (pintype "passive"))
      (node (ref "C212") (pin "1") (pinfunction "1_1") (pintype "passive"))
      (node (ref "C213") (pin "1") (pinfunction "1_1") (pintype "passive"))
      (node (ref "C214") (pin "1") (pinfunction "1_1") (pintype "passive"))
      (node (ref "C215") (pin "1") (pinfunction "1_1") (pintype "passive"))
      (node (ref "C216") (pin "1") (pinfunction "1_1") (pintype "passive"))
      (node (ref "C217") (pin "1") (pinfunction "1_1") (pintype "passive"))
      (node (ref "C218") (pin "1") (pinfunction "1_1") (pintype "passive"))
      (node (ref "ENC201") (pin "3") (pinfunction "3_3") (pintype "passive"))
      (node (ref "ENC201") (pin "4") (pinfunction "4_4") (pintype "passive"))
      (node (ref "ENC201") (pin "C") (pinfunction "C_C") (pintype "passive"))
      (node (ref "ENC202") (pin "3") (pinfunction "3_3") (pintype "passive"))
      (node (ref "ENC202") (pin "4") (pinfunction "4_4") (pintype "passive"))
      (node (ref "ENC202") (pin "C") (pinfunction "C_C") (pintype "passive"))
      (node (ref "ENC203") (pin "3") (pinfunction "3_3") (pintype "passive"))
      (node (ref "ENC203") (pin "4") (pinfunction "4_4") (pintype "passive"))
      (node (ref "ENC203") (pin "C") (pinfunction "C_C") (pintype "passive"))
      (node (ref "LED201") (pin "3") (pinfunction "GND_3") (pintype "passive"))
      (node (ref "LED202") (pin "3") (pinfunction "GND_3") (pintype "passive"))
      (node (ref "LED203") (pin "3") (pinfunction "GND_3") (pintype "passive"))
      (node (ref "LED204") (pin "3") (pinfunction "GND_3") (pintype "passive"))
      (node (ref "LED205") (pin "3") (pinfunction "GND_3") (pintype "passive"))
      (node (ref "LED206") (pin "3") (pinfunction "GND_3") (pintype "passive"))
      (node (ref "LED207") (pin "3") (pinfunction "GND_3") (pintype "passive"))
      (node (ref "LED208") (pin "3") (pinfunction "GND_3") (pintype "passive"))
      (node (ref "LED209") (pin "3") (pinfunction "GND_3") (pintype "passive"))
      (node (ref "MH201") (pin "1") (pinfunction "1_1") (pintype "passive"))
      (node (ref "MH202") (pin "1") (pinfunction "1_1") (pintype "passive"))
      (node (ref "MH203") (pin "1") (pinfunction "1_1") (pintype "passive"))
      (node (ref "MH204") (pin "1") (pinfunction "1_1") (pintype "passive"))
      (node (ref "MH205") (pin "1") (pinfunction "1_1") (pintype "passive"))
      (node (ref "MH206") (pin "1") (pinfunction "1_1") (pintype "passive"))
      (node (ref "MH207") (pin "1") (pinfunction "1_1") (pintype "passive"))
      (node (ref "MH208") (pin "1") (pinfunction "1_1") (pintype "passive"))
    )
    (net (code "29") (name "Net-(D201-A)") (class "Default")
      (node (ref "D201") (pin "2") (pinfunction "A_2") (pintype "passive"))
      (node (ref "J201") (pin "2") (pinfunction "2_2") (pintype "passive"))
    )
    (net (code "30") (name "Net-(D202-A)") (class "Default")
      (node (ref "D202") (pin "2") (pinfunction "A_2") (pintype "passive"))
      (node (ref "J202") (pin "2") (pinfunction "2_2") (pintype "passive"))
    )
    (net (code "31") (name "Net-(D203-A)") (class "Default")
      (node (ref "D203") (pin "2") (pinfunction "A_2") (pintype "passive"))
      (node (ref "J203") (pin "2") (pinfunction "2_2") (pintype "passive"))
    )
    (net (code "32") (name "Net-(D204-A)") (class "Default")
      (node (ref "D204") (pin "2") (pinfunction "A_2") (pintype "passive"))
      (node (ref "J204") (pin "2") (pinfunction "2_2") (pintype "passive"))
    )
    (net (code "33") (name "Net-(D205-A)") (class "Default")
      (node (ref "D205") (pin "2") (pinfunction "A_2") (pintype "passive"))
      (node (ref "J205") (pin "2") (pinfunction "2_2") (pintype "passive"))
    )
    (net (code "34") (name "Net-(D206-A)") (class "Default")
      (node (ref "D206") (pin "2") (pinfunction "A_2") (pintype "passive"))
      (node (ref "J206") (pin "2") (pinfunction "2_2") (pintype "passive"))
    )
    (net (code "35") (name "Net-(D207-A)") (class "Default")
      (node (ref "D207") (pin "2") (pinfunction "A_2") (pintype "passive"))
      (node (ref "J207") (pin "2") (pinfunction "2_2") (pintype "passive"))
    )
    (net (code "36") (name "Net-(D208-A)") (class "Default")
      (node (ref "D208") (pin "2") (pinfunction "A_2") (pintype "passive"))
      (node (ref "J208") (pin "2") (pinfunction "2_2") (pintype "passive"))
    )
    (net (code "37") (name "Net-(D209-A)") (class "Default")
      (node (ref "D209") (pin "2") (pinfunction "A_2") (pintype "passive"))
      (node (ref "J209") (pin "2") (pinfunction "2_2") (pintype "passive"))
    )
    (net (code "38") (name "Net-(ENC201-PadA)") (class "Default")
      (node (ref "ENC201") (pin "A") (pinfunction "A_A") (pintype "passive"))
      (node (ref "R201") (pin "1") (pinfunction "1_1") (pintype "passive"))
      (node (ref "R203") (pin "2") (pinfunction "2_2") (pintype "passive"))
    )
    (net (code "39") (name "Net-(ENC201-PadB)") (class "Default")
      (node (ref "ENC201") (pin "B") (pinfunction "B_B") (pintype "passive"))
      (node (ref "R202") (pin "1") (pinfunction "1_1") (pintype "passive"))
      (node (ref "R204") (pin "2") (pinfunction "2_2") (pintype "passive"))
    )
    (net (code "40") (name "Net-(ENC202-PadA)") (class "Default")
      (node (ref "ENC202") (pin "A") (pinfunction "A_A") (pintype "passive"))
      (node (ref "R205") (pin "1") (pinfunction "1_1") (pintype "passive"))
      (node (ref "R207") (pin "2") (pinfunction "2_2") (pintype "passive"))
    )
    (net (code "41") (name "Net-(ENC202-PadB)") (class "Default")
      (node (ref "ENC202") (pin "B") (pinfunction "B_B") (pintype "passive"))
      (node (ref "R206") (pin "1") (pinfunction "1_1") (pintype "passive"))
      (node (ref "R208") (pin "2") (pinfunction "2_2") (pintype "passive"))
    )
    (net (code "42") (name "Net-(ENC203-PadA)") (class "Default")
      (node (ref "ENC203") (pin "A") (pinfunction "A_A") (pintype "passive"))
      (node (ref "R209") (pin "1") (pinfunction "1_1") (pintype "passive"))
      (node (ref "R211") (pin "2") (pinfunction "2_2") (pintype "passive"))
    )
    (net (code "43") (name "Net-(ENC203-PadB)") (class "Default")
      (node (ref "ENC203") (pin "B") (pinfunction "B_B") (pintype "passive"))
      (node (ref "R210") (pin "1") (pinfunction "1_1") (pintype "passive"))
      (node (ref "R212") (pin "2") (pinfunction "2_2") (pintype "passive"))
    )
    (net (code "44") (name "unconnected-(LED209-DOUT-Pad2)") (class "Default")
      (node (ref "LED209") (pin "2") (pinfunction "DOUT_2") (pintype "passive+no_connect"))
    )
  )
)
